# Power_Switch.net
KiCad netlist of a schematic drawn in Altium Designer
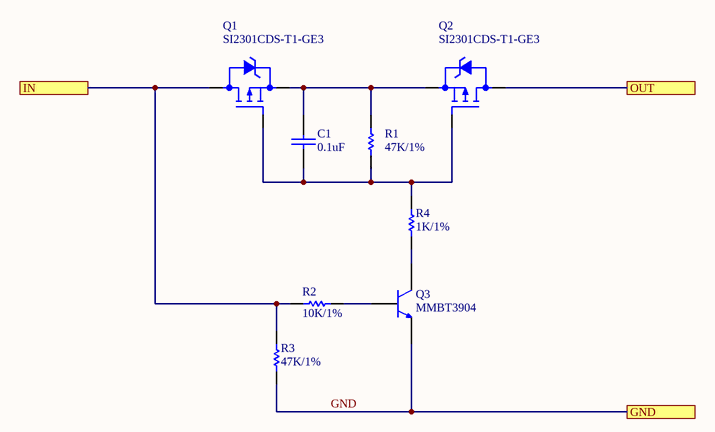
[diagram p0: Power_Switch.SchDoc]

(export (version "E")
  (design (tool "Eeschema 10.0.6"))
  (components
    (comp (ref "C1")
      (value "0.1uF")
      (footprint "0805-CAP-TDK")
      (libsource (lib "LIB2022 - Passives") (part "CAP-SMD"))
    )
    (comp (ref "Q1")
      (value "SI2301CDS-T1-GE3")
      (footprint "VS-SOT-23")
      (description "P-Channel 20 V 3.1A (Tc) 860mW (Ta), 1.6W (Tc) Surface Mount SOT-23-3 (TO-236)")
      (libsource (lib "") (part "SI2301CDS-T1-GE3_1"))
    )
    (comp (ref "Q2")
      (value "SI2301CDS-T1-GE3")
      (footprint "VS-SOT-23")
      (description "P-Channel 20 V 3.1A (Tc) 860mW (Ta), 1.6W (Tc) Surface Mount SOT-23-3 (TO-236)")
      (libsource (lib "LIB2022 - Semiconductors") (part "SI2301CDS-T1-GE3"))
    )
    (comp (ref "Q3")
      (value "MMBT3904")
      (footprint "VS-SOT-23")
      (description "Bipolar (BJT) Transistor NPN 40 V 200 mA 300MHz 350 mW Surface Mount SOT-23")
      (libsource (lib "LIB2022 - Semiconductors") (part "MMBT3904"))
    )
    (comp (ref "R1")
      (value "47K/1%")
      (footprint "0805-RES-PANASONIC")
      (libsource (lib "LIB2022 - Passives") (part "RES-SMD"))
    )
    (comp (ref "R2")
      (value "10K/1%")
      (footprint "0805-RES-PANASONIC")
      (libsource (lib "LIB2022 - Passives") (part "RES-SMD"))
    )
    (comp (ref "R3")
      (value "47K/1%")
      (footprint "0805-RES-PANASONIC")
      (libsource (lib "LIB2022 - Passives") (part "RES-SMD"))
    )
    (comp (ref "R4")
      (value "1K/1%")
      (footprint "0805-RES-PANASONIC")
      (libsource (lib "LIB2022 - Passives") (part "RES-SMD"))
    )
  )
  (nets
    (net (code "1") (name "/GND") (class "Default")
      (node (ref "Q3") (pin "2") (pinfunction "E_2") (pintype "passive"))
      (node (ref "R3") (pin "1") (pinfunction "1_1") (pintype "passive"))
    )
    (net (code "2") (name "/IN") (class "Default")
      (node (ref "Q1") (pin "3") (pinfunction "D_3") (pintype "passive"))
      (node (ref "R2") (pin "1") (pinfunction "1_1") (pintype "passive"))
      (node (ref "R3") (pin "2") (pinfunction "2_2") (pintype "passive"))
    )
    (net (code "3") (name "/OUT") (class "Default")
      (node (ref "Q2") (pin "3") (pinfunction "D_3") (pintype "passive"))
    )
    (net (code "4") (name "Net-(Q1-G)") (class "Default")
      (node (ref "C1") (pin "1") (pinfunction "1_1") (pintype "passive"))
      (node (ref "Q1") (pin "1") (pinfunction "G_1") (pintype "passive"))
      (node (ref "Q2") (pin "1") (pinfunction "G_1") (pintype "passive"))
      (node (ref "R1") (pin "1") (pinfunction "1_1") (pintype "passive"))
      (node (ref "R4") (pin "2") (pinfunction "2_2") (pintype "passive"))
    )
    (net (code "5") (name "Net-(Q1-S)") (class "Default")
      (node (ref "C1") (pin "2") (pinfunction "2_2") (pintype "passive"))
      (node (ref "Q1") (pin "2") (pinfunction "S_2") (pintype "passive"))
      (node (ref "Q2") (pin "2") (pinfunction "S_2") (pintype "passive"))
      (node (ref "R1") (pin "2") (pinfunction "2_2") (pintype "passive"))
    )
    (net (code "6") (name "Net-(Q3-B)") (class "Default")
      (node (ref "Q3") (pin "1") (pinfunction "B_1") (pintype "passive"))
      (node (ref "R2") (pin "2") (pinfunction "2_2") (pintype "passive"))
    )
    (net (code "7") (name "Net-(Q3-C)") (class "Default")
      (node (ref "Q3") (pin "3") (pinfunction "C_3") (pintype "passive"))
      (node (ref "R4") (pin "1") (pinfunction "1_1") (pintype "passive"))
    )
  )
)
